# fourLEDS.net
KiCad netlist of a schematic drawn in Altium Designer
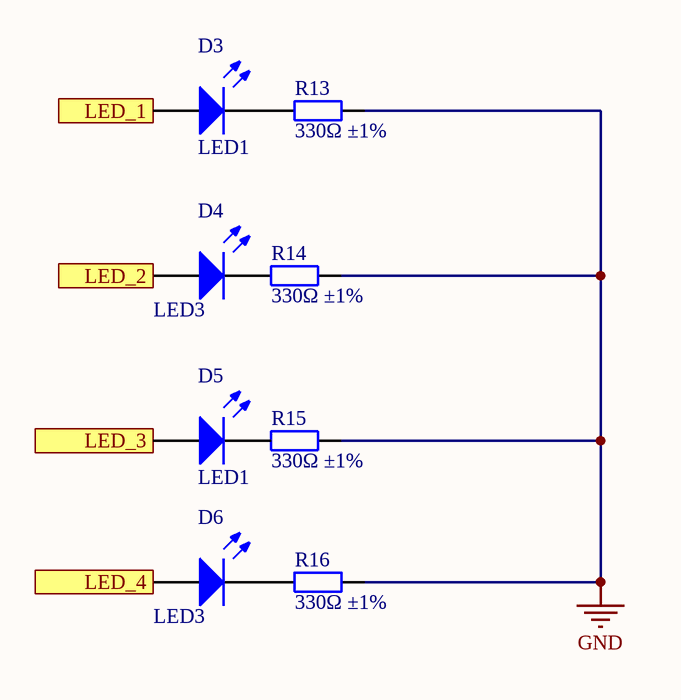
[diagram p0: fourLEDS.SchDoc]

(export (version "E")
  (design (tool "Eeschema 10.0.6"))
  (components
    (comp (ref "D3")
      (value "LED1")
      (footprint "LED-1")
      (description "Typical RED GaAs LED")
      (fields (field (name "PUBLISHER") "Altium Limited"))
      (libsource (lib "Miscellaneous Devices") (part "LED1"))
    )
    (comp (ref "D4")
      (value "LED3")
      (footprint "3.5X2.8X1.9")
      (description "Typical BLUE SiC LED")
      (fields (field (name "PUBLISHER") "Altium Limited"))
      (libsource (lib "Miscellaneous Devices") (part "LED3"))
    )
    (comp (ref "D5")
      (value "LED1")
      (footprint "LED-1")
      (description "Typical RED GaAs LED")
      (fields (field (name "PUBLISHER") "Altium Limited"))
      (libsource (lib "Miscellaneous Devices") (part "LED1"))
    )
    (comp (ref "D6")
      (value "LED3")
      (footprint "3.5X2.8X1.9")
      (description "Typical BLUE SiC LED")
      (fields (field (name "PUBLISHER") "Altium Limited"))
      (libsource (lib "Miscellaneous Devices") (part "LED3"))
    )
    (comp (ref "R13")
      (value "330Ω ±1%")
      (footprint "0603_R")
      (description "Chip resistor")
      (fields (field (name "MANUFACTURER") "Uniroyal Elec") (field (name "PARTNUMBER") "0603WAF3300T5E"))
      (libsource (lib "RES") (part "0603 330R (3300) 1%"))
    )
    (comp (ref "R14")
      (value "330Ω ±1%")
      (footprint "0603_R")
      (description "Chip resistor")
      (fields (field (name "MANUFACTURER") "Uniroyal Elec") (field (name "PARTNUMBER") "0603WAF3300T5E"))
      (libsource (lib "RES") (part "0603 330R (3300) 1%"))
    )
    (comp (ref "R15")
      (value "330Ω ±1%")
      (footprint "0603_R")
      (description "Chip resistor")
      (fields (field (name "MANUFACTURER") "Uniroyal Elec") (field (name "PARTNUMBER") "0603WAF3300T5E"))
      (libsource (lib "RES") (part "0603 330R (3300) 1%"))
    )
    (comp (ref "R16")
      (value "330Ω ±1%")
      (footprint "0603_R")
      (description "Chip resistor")
      (fields (field (name "MANUFACTURER") "Uniroyal Elec") (field (name "PARTNUMBER") "0603WAF3300T5E"))
      (libsource (lib "RES") (part "0603 330R (3300) 1%"))
    )
  )
  (nets
    (net (code "1") (name "/LED_1") (class "Default")
      (node (ref "D3") (pin "1") (pinfunction "A_1") (pintype "passive"))
    )
    (net (code "2") (name "/LED_2") (class "Default")
      (node (ref "D4") (pin "1") (pinfunction "A_1") (pintype "passive"))
    )
    (net (code "3") (name "/LED_3") (class "Default")
      (node (ref "D5") (pin "1") (pinfunction "A_1") (pintype "passive"))
    )
    (net (code "4") (name "/LED_4") (class "Default")
      (node (ref "D6") (pin "1") (pinfunction "A_1") (pintype "passive"))
    )
    (net (code "5") (name "GND") (class "Default")
      (node (ref "R13") (pin "2") (pinfunction "2_2") (pintype "passive"))
      (node (ref "R14") (pin "2") (pinfunction "2_2") (pintype "passive"))
      (node (ref "R15") (pin "2") (pinfunction "2_2") (pintype "passive"))
      (node (ref "R16") (pin "2") (pinfunction "2_2") (pintype "passive"))
    )
    (net (code "6") (name "Net-(D3-K)") (class "Default")
      (node (ref "D3") (pin "2") (pinfunction "K_2") (pintype "passive"))
      (node (ref "R13") (pin "1") (pinfunction "1_1") (pintype "passive"))
    )
    (net (code "7") (name "Net-(D6-K)") (class "Default")
      (node (ref "D6") (pin "2") (pinfunction "K_2") (pintype "passive"))
      (node (ref "R16") (pin "1") (pinfunction "1_1") (pintype "passive"))
    )
    (net (code "8") (name "unconnected-(D4-K-Pad2)") (class "Default")
      (node (ref "D4") (pin "2") (pinfunction "K_2") (pintype "passive"))
    )
    (net (code "9") (name "unconnected-(D5-K-Pad2)") (class "Default")
      (node (ref "D5") (pin "2") (pinfunction "K_2") (pintype "passive"))
    )
    (net (code "10") (name "unconnected-(R14-Pad1)") (class "Default")
      (node (ref "R14") (pin "1") (pinfunction "1_1") (pintype "passive"))
    )
    (net (code "11") (name "unconnected-(R15-Pad1)") (class "Default")
      (node (ref "R15") (pin "1") (pinfunction "1_1") (pintype "passive"))
    )
  )
)
